# File_Nguyen_ly.net
KiCad netlist of a schematic drawn in Altium Designer
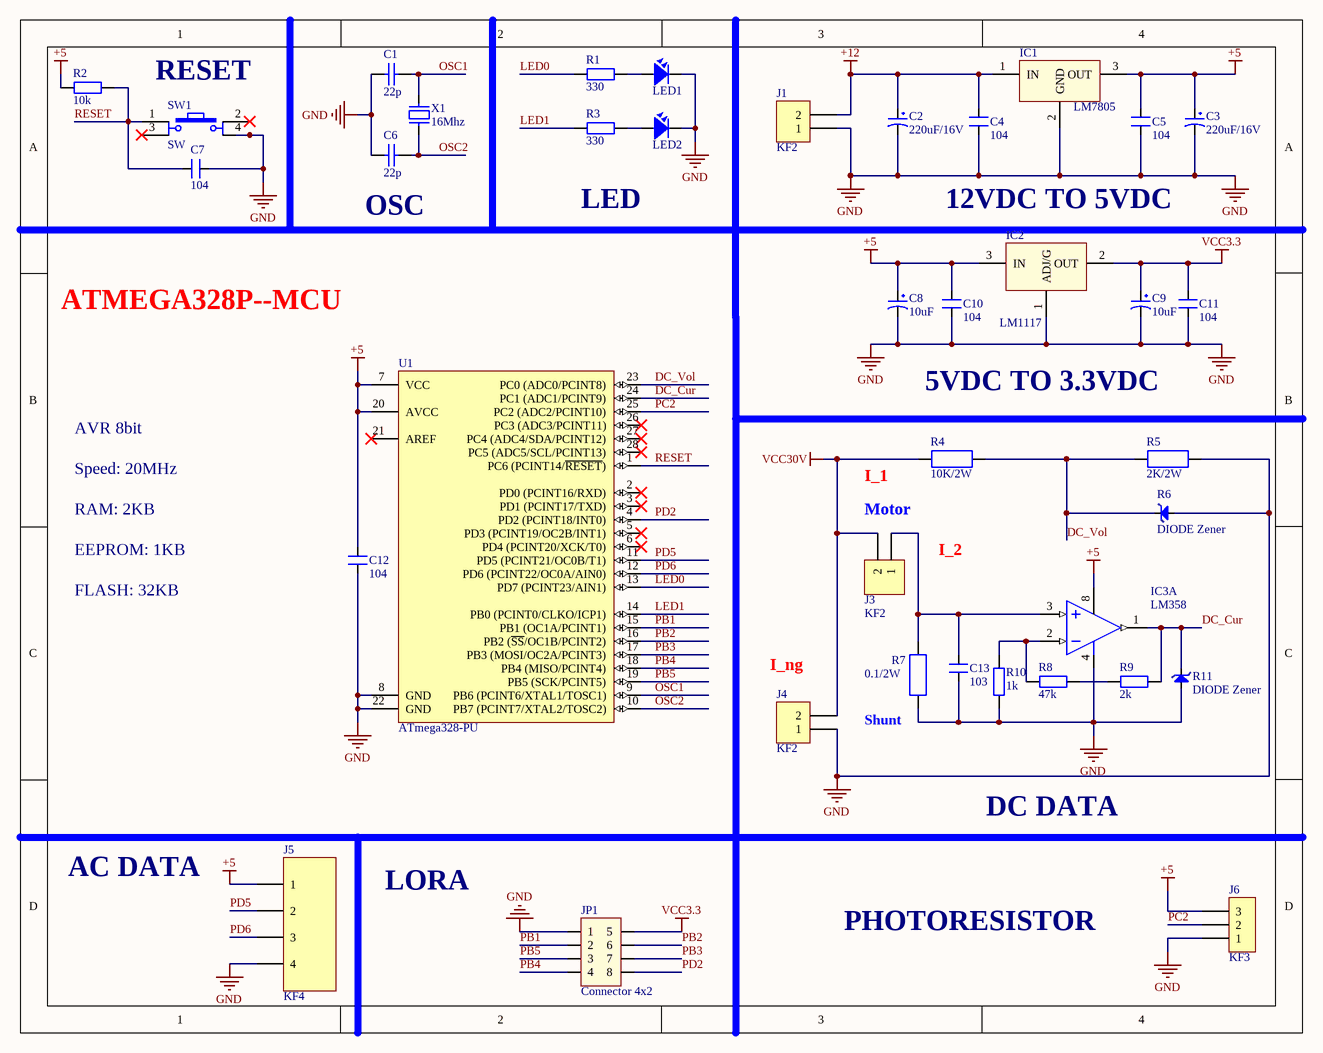
[diagram p0: File_Nguyen_ly.SchDoc]

(export (version "E")
  (design (tool "Eeschema 10.0.6"))
  (components
    (comp (ref "C1")
      (value "22p")
      (footprint "Tu-pico")
      (description "Capacitor")
      (fields (field (name "Comment") "Capacitor Ceramic") (field (name "PUBLISHER") "Altium Limited"))
      (libsource (lib "hphonglib") (part "CapCeramic"))
    )
    (comp (ref "C2")
      (value "220uF/16V")
      (footprint "CP1.5/3.4")
      (description "Cap 100uF/35V - 470uF/16V")
      (libsource (lib "syhaunguyen") (part "CP3"))
    )
    (comp (ref "C3")
      (value "220uF/16V")
      (footprint "CP1.5/3.4")
      (description "Cap 100uF/35V - 470uF/16V")
      (libsource (lib "syhaunguyen") (part "CP3"))
    )
    (comp (ref "C4")
      (value "104")
      (footprint "CN2")
      (description "Cap np 104 => 105pF")
      (libsource (lib "syhaunguyen") (part "CN2"))
    )
    (comp (ref "C5")
      (value "104")
      (footprint "CN2")
      (description "Cap np 104 => 105pF")
      (libsource (lib "syhaunguyen") (part "CN2"))
    )
    (comp (ref "C6")
      (value "22p")
      (footprint "Tu-pico")
      (description "Capacitor")
      (fields (field (name "Comment") "Capacitor Ceramic") (field (name "PUBLISHER") "Altium Limited"))
      (libsource (lib "hphonglib") (part "CapCeramic"))
    )
    (comp (ref "C7")
      (value "104")
      (footprint "CN2")
      (description "Cap np 104 => 105pF")
      (libsource (lib "syhaunguyen") (part "CN2"))
    )
    (comp (ref "C8")
      (value "10uF")
      (footprint "CP1/2")
      (description "Cap P  0,1uF < 22uF , 16 - 50V")
      (libsource (lib "syhaunguyen") (part "CP1"))
    )
    (comp (ref "C9")
      (value "10uF")
      (footprint "CP1/2")
      (description "Cap P  0,1uF < 22uF , 16 - 50V")
      (libsource (lib "syhaunguyen") (part "CP1"))
    )
    (comp (ref "C10")
      (value "104")
      (footprint "CN2")
      (description "Cap np 104 => 105pF")
      (libsource (lib "syhaunguyen") (part "CN2"))
    )
    (comp (ref "C11")
      (value "104")
      (footprint "CN2")
      (description "Cap np 104 => 105pF")
      (libsource (lib "syhaunguyen") (part "CN2"))
    )
    (comp (ref "C12")
      (value "104")
      (footprint "CN2")
      (description "Cap np 104 => 105pF")
      (libsource (lib "syhaunguyen") (part "CN2"))
    )
    (comp (ref "C13")
      (value "103")
      (footprint "CN1.5")
      (description "Cap np 682pF => 104pF")
      (libsource (lib "My Library") (part "CN1.5"))
    )
    (comp (ref "IC1")
      (value "LM7805")
      (footprint "QTO-220")
      (description "On ap +, from + 5 to + 24VDC")
      (libsource (lib "syhaunguyen") (part "LM78xx"))
    )
    (comp (ref "IC2")
      (value "LM1117")
      (footprint "SOT223-4N")
      (description "Available in 1.8V, 2.5V, 2.85V, 3.3V, 5V, and  Adjustable Versions")
      (libsource (lib "syhaunguyen") (part "LM1117"))
    )
    (comp (ref "IC3")
      (value "LM358")
      (footprint "DIP8/W0.3")
      (description "Low-Power Dual Operational Amplifier")
      (libsource (lib "syhaunguyen") (part "LM358"))
    )
    (comp (ref "J1")
      (value "KF2")
      (footprint "KF2-5.08")
      (fields
        (field (name "MANUFACTURER") "Würth Elektronik eiSos GmbH")
        (field (name "PARTNO") "691103110002")
        (field (name "CREATED BY") "Karrer Zheng")
      )
      (libsource (lib "LIBRARY1") (part "KF2"))
    )
    (comp (ref "J3")
      (value "KF2")
      (footprint "KF2-5.08")
      (fields
        (field (name "MANUFACTURER") "Würth Elektronik eiSos GmbH")
        (field (name "PARTNO") "691103110002")
        (field (name "CREATED BY") "Karrer Zheng")
      )
      (libsource (lib "") (part "KF2_1"))
    )
    (comp (ref "J4")
      (value "KF2")
      (footprint "KF2-5.08")
      (fields
        (field (name "MANUFACTURER") "Würth Elektronik eiSos GmbH")
        (field (name "PARTNO") "691103110002")
        (field (name "CREATED BY") "Karrer Zheng")
      )
      (libsource (lib "LIBRARY1") (part "KF2"))
    )
    (comp (ref "J5")
      (value "KF4")
      (footprint "KF4-5")
      (fields
        (field (name "MANUFACTURER") "Würth Elektronik eiSos GmbH")
        (field (name "PARTNO") "691133710004")
        (field (name "CREATED BY") "Baojun Chen")
      )
      (libsource (lib "LIBRARY1") (part "KF4"))
    )
    (comp (ref "J6")
      (value "KF3")
      (footprint "KF3-5.08")
      (fields
        (field (name "MANUFACTURER") "Würth Elektronik eiSos GmbH")
        (field (name "PARTNO") "691103110003")
        (field (name "CREATED BY") "Karrer Zheng")
      )
      (libsource (lib "TechMT.VN_Lib_Project v2") (part "KF3"))
    )
    (comp (ref "JP1") (value "Connector 4x2") (footprint "JP4x2") (libsource (lib "Cty1") (part "JP4x2")))
    (comp (ref "LED1")
      (value "LED")
      (footprint "LED-5-Yellow")
      (description "LED Single colour Green and Red")
      (libsource (lib "syhaunguyen") (part "LED"))
    )
    (comp (ref "LED2")
      (value "LED")
      (footprint "LED-5-BLUE")
      (description "LED Single colour Green and Red")
      (libsource (lib "syhaunguyen") (part "LED"))
    )
    (comp (ref "R1")
      (value "330")
      (footprint "R1/4W")
      (description "Resistor 1/4W")
      (libsource (lib "hphonglib") (part "R1/4W"))
    )
    (comp (ref "R2")
      (value "10k")
      (footprint "R1/4W")
      (description "Resistor 1/4W")
      (libsource (lib "hphonglib") (part "R1/4W"))
    )
    (comp (ref "R3")
      (value "330")
      (footprint "R1/4W")
      (description "Resistor 1/4W")
      (libsource (lib "hphonglib") (part "R1/4W"))
    )
    (comp (ref "R4")
      (value "10K/2W")
      (footprint "R2W")
      (description "Resistor 2W")
      (libsource (lib "syhaunguyen") (part "R2W"))
    )
    (comp (ref "R5")
      (value "2K/2W")
      (footprint "R2W")
      (description "Resistor 2W")
      (libsource (lib "syhaunguyen") (part "R2W"))
    )
    (comp (ref "R6")
      (value "DIODE Zener")
      (footprint "DIO-2A-ZEN")
      (description "Zenner")
      (libsource (lib "TechMT.VN_Lib_Project v2") (part "DIODE Zener"))
    )
    (comp (ref "R7")
      (value "0.1/2W")
      (footprint "R2W")
      (description "Resistor 2W")
      (libsource (lib "syhaunguyen") (part "R2W"))
    )
    (comp (ref "R8")
      (value "47k")
      (footprint "R1/4W")
      (description "Resistor 1/4W")
      (libsource (lib "syhaunguyen") (part "R1/4W"))
    )
    (comp (ref "R9")
      (value "2k")
      (footprint "R1/4W")
      (description "Resistor 1/4W")
      (libsource (lib "syhaunguyen") (part "R1/4W"))
    )
    (comp (ref "R10")
      (value "1k")
      (footprint "R1/4W")
      (description "Resistor 1/4W")
      (libsource (lib "syhaunguyen") (part "R1/4W"))
    )
    (comp (ref "R11")
      (value "DIODE Zener")
      (footprint "DIO-2A-ZEN")
      (description "Zenner")
      (libsource (lib "TechMT.VN_Lib_Project v2") (part "DIODE Zener"))
    )
    (comp (ref "SW1")
      (value "SW")
      (footprint "SW4")
      (description "Switch button 4 pin")
      (libsource (lib "syhaunguyen") (part "SW4"))
    )
    (comp (ref "U1")
      (value "ATmega328-PU")
      (footprint "DIP28")
      (fields (field (name "PUBLISHER") "Altium Limited"))
      (libsource (lib "LIBRARY1") (part "ATmega328-PU"))
    )
    (comp (ref "X1")
      (value "16Mhz")
      (footprint "XT2")
      (description "Crystal For all Crystal 2pin.")
      (libsource (lib "syhaunguyen") (part "XT2"))
    )
  )
  (nets
    (net (code "1") (name "+5") (class "Default")
      (node (ref "C10") (pin "2") (pinfunction "2_2") (pintype "passive"))
      (node (ref "C12") (pin "2") (pinfunction "2_2") (pintype "passive"))
      (node (ref "C3") (pin "1") (pinfunction "1_1") (pintype "passive"))
      (node (ref "C5") (pin "2") (pinfunction "2_2") (pintype "passive"))
      (node (ref "C8") (pin "1") (pinfunction "1_1") (pintype "passive"))
      (node (ref "IC1") (pin "3") (pinfunction "OUT_3") (pintype "passive"))
      (node (ref "IC2") (pin "3") (pinfunction "IN_3") (pintype "passive"))
      (node (ref "IC3") (pin "8") (pinfunction "+V_8") (pintype "passive"))
      (node (ref "J5") (pin "1") (pinfunction "1_1") (pintype "passive"))
      (node (ref "J6") (pin "3") (pinfunction "3_3") (pintype "passive"))
      (node (ref "R2") (pin "2") (pinfunction "2_2") (pintype "passive"))
      (node (ref "U1") (pin "20") (pinfunction "AVCC_20") (pintype "power_in"))
      (node (ref "U1") (pin "7") (pinfunction "VCC_7") (pintype "power_in"))
    )
    (net (code "2") (name "+12") (class "Default")
      (node (ref "C2") (pin "1") (pinfunction "1_1") (pintype "passive"))
      (node (ref "C4") (pin "2") (pinfunction "2_2") (pintype "passive"))
      (node (ref "IC1") (pin "1") (pinfunction "IN_1") (pintype "passive"))
      (node (ref "J1") (pin "2") (pinfunction "2_2") (pintype "passive"))
    )
    (net (code "3") (name "/DC_Cur") (class "Default")
      (node (ref "IC3") (pin "1") (pinfunction "OUT_1") (pintype "output"))
      (node (ref "R11") (pin "2") (pinfunction "K_2") (pintype "passive"))
      (node (ref "R9") (pin "2") (pinfunction "2_2") (pintype "passive"))
      (node (ref "U1") (pin "24") (pinfunction "PC1_(ADC1/PCINT9)_24") (pintype "bidirectional"))
    )
    (net (code "4") (name "/DC_Vol") (class "Default")
      (node (ref "R4") (pin "1") (pinfunction "1_1") (pintype "passive"))
      (node (ref "R5") (pin "2") (pinfunction "2_2") (pintype "passive"))
      (node (ref "R6") (pin "2") (pinfunction "K_2") (pintype "passive"))
      (node (ref "U1") (pin "23") (pinfunction "PC0_(ADC0/PCINT8)_23") (pintype "bidirectional"))
    )
    (net (code "5") (name "/LED0") (class "Default")
      (node (ref "R1") (pin "1") (pinfunction "1_1") (pintype "passive"))
      (node (ref "U1") (pin "13") (pinfunction "PD7_(PCINT23/AIN1)_13") (pintype "bidirectional"))
    )
    (net (code "6") (name "/LED1") (class "Default")
      (node (ref "R3") (pin "1") (pinfunction "1_1") (pintype "passive"))
      (node (ref "U1") (pin "14") (pinfunction "PB0_(PCINT0/CLKO/ICP1)_14") (pintype "bidirectional"))
    )
    (net (code "7") (name "/OSC1") (class "Default")
      (node (ref "C1") (pin "2") (pinfunction "2_2") (pintype "passive"))
      (node (ref "U1") (pin "9") (pinfunction "PB6_(PCINT6/XTAL1/TOSC1)_9") (pintype "bidirectional"))
      (node (ref "X1") (pin "2") (pinfunction "2_2") (pintype "passive"))
    )
    (net (code "8") (name "/OSC2") (class "Default")
      (node (ref "C6") (pin "2") (pinfunction "2_2") (pintype "passive"))
      (node (ref "U1") (pin "10") (pinfunction "PB7_(PCINT7/XTAL2/TOSC2)_10") (pintype "bidirectional"))
      (node (ref "X1") (pin "1") (pinfunction "1_1") (pintype "passive"))
    )
    (net (code "9") (name "/PB1") (class "Default")
      (node (ref "JP1") (pin "2") (pinfunction "2_2") (pintype "passive"))
      (node (ref "U1") (pin "15") (pinfunction "PB1_(OC1A/PCINT1)_15") (pintype "bidirectional"))
    )
    (net (code "10") (name "/PB2") (class "Default")
      (node (ref "JP1") (pin "6") (pinfunction "6_6") (pintype "passive"))
      (node (ref "U1") (pin "16") (pinfunction "PB2_(~{SS}/OC1B/PCINT2)_16") (pintype "bidirectional"))
    )
    (net (code "11") (name "/PB3") (class "Default")
      (node (ref "JP1") (pin "7") (pinfunction "7_7") (pintype "passive"))
      (node (ref "U1") (pin "17") (pinfunction "PB3_(MOSI/OC2A/PCINT3)_17") (pintype "bidirectional"))
    )
    (net (code "12") (name "/PB4") (class "Default")
      (node (ref "JP1") (pin "4") (pinfunction "4_4") (pintype "passive"))
      (node (ref "U1") (pin "18") (pinfunction "PB4_(MISO/PCINT4)_18") (pintype "bidirectional"))
    )
    (net (code "13") (name "/PB5") (class "Default")
      (node (ref "JP1") (pin "3") (pinfunction "3_3") (pintype "passive"))
      (node (ref "U1") (pin "19") (pinfunction "PB5_(SCK/PCINT5)_19") (pintype "bidirectional"))
    )
    (net (code "14") (name "/PC2") (class "Default")
      (node (ref "J6") (pin "2") (pinfunction "2_2") (pintype "passive"))
      (node (ref "U1") (pin "25") (pinfunction "PC2_(ADC2/PCINT10)_25") (pintype "bidirectional"))
    )
    (net (code "15") (name "/PD2") (class "Default")
      (node (ref "JP1") (pin "8") (pinfunction "8_8") (pintype "passive"))
      (node (ref "U1") (pin "4") (pinfunction "PD2_(PCINT18/INT0)_4") (pintype "bidirectional"))
    )
    (net (code "16") (name "/PD5") (class "Default")
      (node (ref "J5") (pin "2") (pinfunction "2_2") (pintype "passive"))
      (node (ref "U1") (pin "11") (pinfunction "PD5_(PCINT21/OC0B/T1)_11") (pintype "bidirectional"))
    )
    (net (code "17") (name "/PD6") (class "Default")
      (node (ref "J5") (pin "3") (pinfunction "3_3") (pintype "passive"))
      (node (ref "U1") (pin "12") (pinfunction "PD6_(PCINT22/OC0A/AIN0)_12") (pintype "bidirectional"))
    )
    (net (code "18") (name "/RESET") (class "Default")
      (node (ref "C7") (pin "1") (pinfunction "1_1") (pintype "passive"))
      (node (ref "R2") (pin "1") (pinfunction "1_1") (pintype "passive"))
      (node (ref "SW1") (pin "1") (pintype "passive"))
      (node (ref "U1") (pin "1") (pinfunction "PC6_(PCINT14/~{RESET})_1") (pintype "bidirectional"))
    )
    (net (code "19") (name "GND") (class "Default")
      (node (ref "C1") (pin "1") (pinfunction "1_1") (pintype "passive"))
      (node (ref "C10") (pin "1") (pinfunction "1_1") (pintype "passive"))
      (node (ref "C11") (pin "1") (pinfunction "1_1") (pintype "passive"))
      (node (ref "C12") (pin "1") (pinfunction "1_1") (pintype "passive"))
      (node (ref "C13") (pin "1") (pinfunction "1_1") (pintype "passive"))
      (node (ref "C2") (pin "2") (pinfunction "2_2") (pintype "passive"))
      (node (ref "C3") (pin "2") (pinfunction "2_2") (pintype "passive"))
      (node (ref "C4") (pin "1") (pinfunction "1_1") (pintype "passive"))
      (node (ref "C5") (pin "1") (pinfunction "1_1") (pintype "passive"))
      (node (ref "C6") (pin "1") (pinfunction "1_1") (pintype "passive"))
      (node (ref "C7") (pin "2") (pinfunction "2_2") (pintype "passive"))
      (node (ref "C8") (pin "2") (pinfunction "2_2") (pintype "passive"))
      (node (ref "C9") (pin "2") (pinfunction "2_2") (pintype "passive"))
      (node (ref "IC1") (pin "2") (pinfunction "GND_2") (pintype "passive"))
      (node (ref "IC2") (pin "1") (pinfunction "ADJ/G_1") (pintype "passive"))
      (node (ref "IC3") (pin "4") (pinfunction "-V_4") (pintype "passive"))
      (node (ref "J1") (pin "1") (pinfunction "1_1") (pintype "passive"))
      (node (ref "J4") (pin "1") (pinfunction "1_1") (pintype "passive"))
      (node (ref "J5") (pin "4") (pinfunction "4_4") (pintype "passive"))
      (node (ref "J6") (pin "1") (pinfunction "1_1") (pintype "passive"))
      (node (ref "JP1") (pin "1") (pinfunction "1_1") (pintype "passive"))
      (node (ref "LED1") (pin "2") (pinfunction "2_2") (pintype "passive"))
      (node (ref "LED2") (pin "2") (pinfunction "2_2") (pintype "passive"))
      (node (ref "R10") (pin "1") (pinfunction "1_1") (pintype "passive"))
      (node (ref "R11") (pin "1") (pinfunction "A_1") (pintype "passive"))
      (node (ref "R5") (pin "1") (pinfunction "1_1") (pintype "passive"))
      (node (ref "R6") (pin "1") (pinfunction "A_1") (pintype "passive"))
      (node (ref "R7") (pin "1") (pinfunction "1_1") (pintype "passive"))
      (node (ref "SW1") (pin "4") (pintype "passive"))
      (node (ref "U1") (pin "22") (pinfunction "GND_22") (pintype "power_in"))
      (node (ref "U1") (pin "8") (pinfunction "GND_8") (pintype "power_in"))
    )
    (net (code "20") (name "Net-(IC3A-IN+)") (class "Default")
      (node (ref "C13") (pin "2") (pinfunction "2_2") (pintype "passive"))
      (node (ref "IC3") (pin "3") (pinfunction "IN+_3") (pintype "input"))
      (node (ref "J3") (pin "1") (pinfunction "1_1") (pintype "passive"))
      (node (ref "R7") (pin "2") (pinfunction "2_2") (pintype "passive"))
    )
    (net (code "21") (name "Net-(IC3A-IN-)") (class "Default")
      (node (ref "IC3") (pin "2") (pinfunction "IN-_2") (pintype "input"))
      (node (ref "R10") (pin "2") (pinfunction "2_2") (pintype "passive"))
      (node (ref "R8") (pin "1") (pinfunction "1_1") (pintype "passive"))
    )
    (net (code "22") (name "Net-(LED1-Pad1)") (class "Default")
      (node (ref "LED1") (pin "1") (pinfunction "1_1") (pintype "passive"))
      (node (ref "R1") (pin "2") (pinfunction "2_2") (pintype "passive"))
    )
    (net (code "23") (name "Net-(LED2-Pad1)") (class "Default")
      (node (ref "LED2") (pin "1") (pinfunction "1_1") (pintype "passive"))
      (node (ref "R3") (pin "2") (pinfunction "2_2") (pintype "passive"))
    )
    (net (code "24") (name "Net-(R8-Pad2)") (class "Default")
      (node (ref "R8") (pin "2") (pinfunction "2_2") (pintype "passive"))
      (node (ref "R9") (pin "1") (pinfunction "1_1") (pintype "passive"))
    )
    (net (code "25") (name "VCC3.3") (class "Default")
      (node (ref "C11") (pin "2") (pinfunction "2_2") (pintype "passive"))
      (node (ref "C9") (pin "1") (pinfunction "1_1") (pintype "passive"))
      (node (ref "IC2") (pin "2") (pinfunction "OUT_2") (pintype "passive"))
      (node (ref "JP1") (pin "5") (pinfunction "5_5") (pintype "passive"))
    )
    (net (code "26") (name "VCC30V") (class "Default")
      (node (ref "J3") (pin "2") (pinfunction "2_2") (pintype "passive"))
      (node (ref "J4") (pin "2") (pinfunction "2_2") (pintype "passive"))
      (node (ref "R4") (pin "2") (pinfunction "2_2") (pintype "passive"))
    )
    (net (code "27") (name "unconnected-(SW1-Pad2)") (class "Default")
      (node (ref "SW1") (pin "2") (pintype "passive+no_connect"))
    )
    (net (code "28") (name "unconnected-(SW1-Pad3)") (class "Default")
      (node (ref "SW1") (pin "3") (pintype "passive+no_connect"))
    )
    (net (code "29") (name "unconnected-(U1-AREF-Pad21)") (class "Default")
      (node (ref "U1") (pin "21") (pinfunction "AREF_21") (pintype "power_in+no_connect"))
    )
    (net (code "30") (name "unconnected-(U1-PC3_(ADC3{slash}PCINT11)-Pad26)") (class "Default")
      (node (ref "U1") (pin "26") (pinfunction "PC3_(ADC3/PCINT11)_26") (pintype "bidirectional+no_connect"))
    )
    (net (code "31") (name "unconnected-(U1-PC4_(ADC4{slash}SDA{slash}PCINT12)-Pad27)") (class "Default")
      (node (ref "U1") (pin "27") (pinfunction "PC4_(ADC4/SDA/PCINT12)_27") (pintype "bidirectional+no_connect"))
    )
    (net (code "32") (name "unconnected-(U1-PC5_(ADC5{slash}SCL{slash}PCINT13)-Pad28)") (class "Default")
      (node (ref "U1") (pin "28") (pinfunction "PC5_(ADC5/SCL/PCINT13)_28") (pintype "bidirectional+no_connect"))
    )
    (net (code "33") (name "unconnected-(U1-PD0_(PCINT16{slash}RXD)-Pad2)") (class "Default")
      (node (ref "U1") (pin "2") (pinfunction "PD0_(PCINT16/RXD)_2") (pintype "bidirectional+no_connect"))
    )
    (net (code "34") (name "unconnected-(U1-PD1_(PCINT17{slash}TXD)-Pad3)") (class "Default")
      (node (ref "U1") (pin "3") (pinfunction "PD1_(PCINT17/TXD)_3") (pintype "bidirectional+no_connect"))
    )
    (net (code "35") (name "unconnected-(U1-PD3_(PCINT19{slash}OC2B{slash}INT1)-Pad5)") (class "Default")
      (node (ref "U1") (pin "5") (pinfunction "PD3_(PCINT19/OC2B/INT1)_5") (pintype "bidirectional+no_connect"))
    )
    (net (code "36") (name "unconnected-(U1-PD4_(PCINT20{slash}XCK{slash}T0)-Pad6)") (class "Default")
      (node (ref "U1") (pin "6") (pinfunction "PD4_(PCINT20/XCK/T0)_6") (pintype "bidirectional+no_connect"))
    )
  )
)
